# wmc.net
KiCad netlist of a schematic drawn in EAGLE
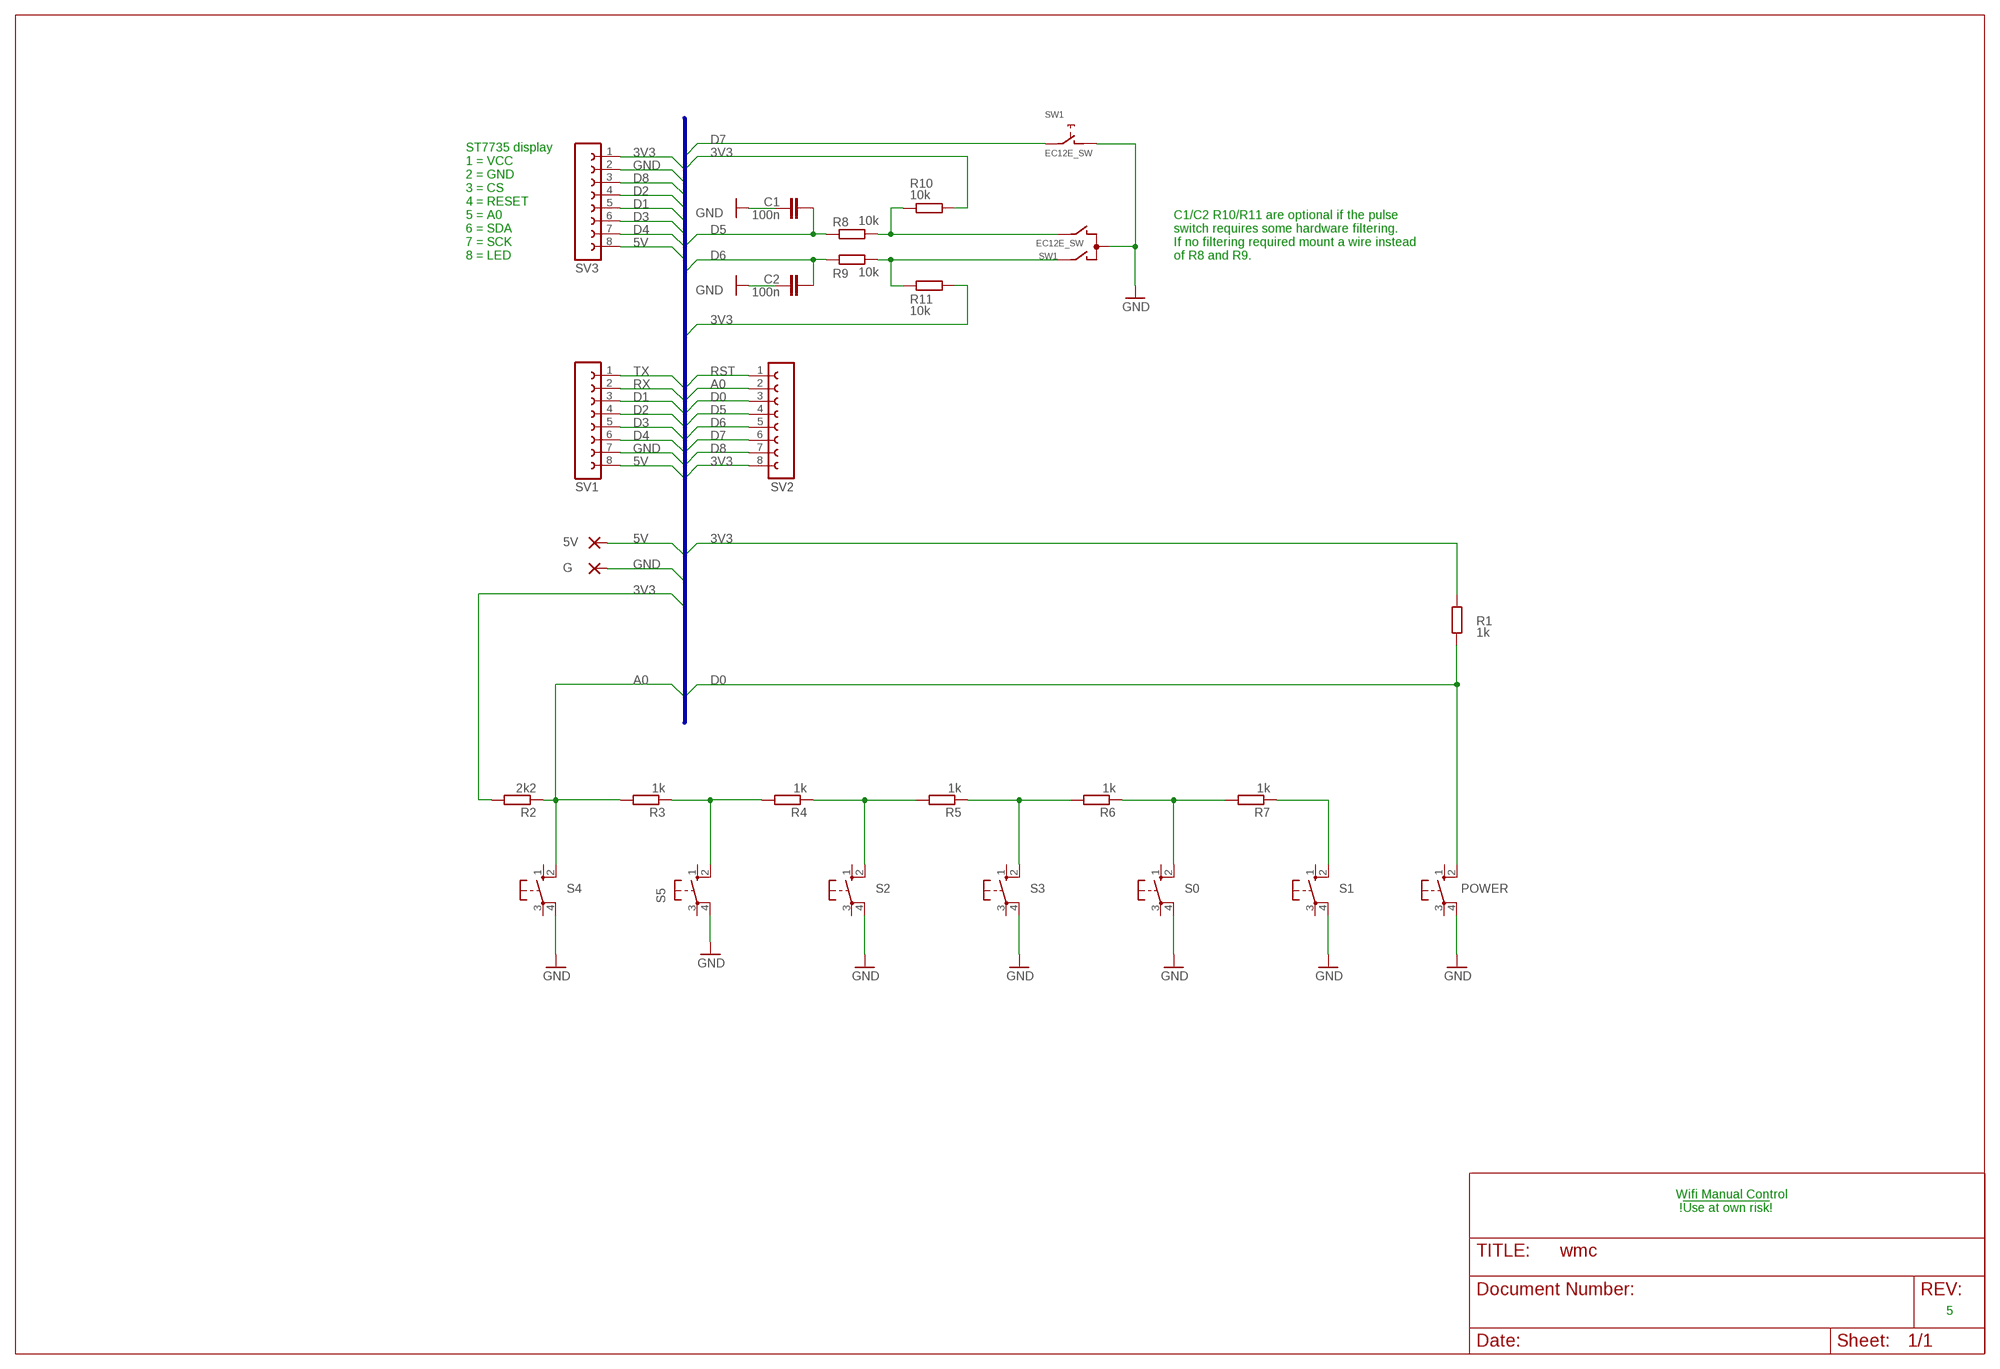
[diagram p0: schematic, sheet 1]

(export (version "E")
  (design (tool "Eeschema 10.0.6"))
  (components
    (comp (ref "5V")
      (value "1,6/0,8")
      (footprint "eagle-import:1,6_0,8")
      (libsource (lib "eagle-import") (part "1,6/0,8"))
    )
    (comp (ref "C1")
      (value "100n")
      (footprint "eagle-import:C025-024X044")
      (libsource (lib "eagle-import") (part "C-EU025-024X044"))
    )
    (comp (ref "C2")
      (value "100n")
      (footprint "eagle-import:C025-024X044")
      (libsource (lib "eagle-import") (part "C-EU025-024X044"))
    )
    (comp (ref "G")
      (value "1,6/0,8")
      (footprint "eagle-import:1,6_0,8")
      (libsource (lib "eagle-import") (part "1,6/0,8"))
    )
    (comp (ref "POWER")
      (value "10-XX")
      (footprint "eagle-import:B3F-10XX")
      (fields (field (name "MPN") "B3F-1000"))
      (libsource (lib "eagle-import") (part "10-XX"))
    )
    (comp (ref "R1")
      (value "1k")
      (footprint "eagle-import:0309_10")
      (libsource (lib "eagle-import") (part "R-EU_0309/10"))
    )
    (comp (ref "R2")
      (value "2k2")
      (footprint "eagle-import:0309_10")
      (libsource (lib "eagle-import") (part "R-EU_0309/10"))
    )
    (comp (ref "R3")
      (value "1k")
      (footprint "eagle-import:0309_10")
      (libsource (lib "eagle-import") (part "R-EU_0309/10"))
    )
    (comp (ref "R4")
      (value "1k")
      (footprint "eagle-import:0309_10")
      (libsource (lib "eagle-import") (part "R-EU_0309/10"))
    )
    (comp (ref "R5")
      (value "1k")
      (footprint "eagle-import:0309_10")
      (libsource (lib "eagle-import") (part "R-EU_0309/10"))
    )
    (comp (ref "R6")
      (value "1k")
      (footprint "eagle-import:0309_10")
      (libsource (lib "eagle-import") (part "R-EU_0309/10"))
    )
    (comp (ref "R7")
      (value "1k")
      (footprint "eagle-import:0309_10")
      (libsource (lib "eagle-import") (part "R-EU_0309/10"))
    )
    (comp (ref "R8")
      (value "10k")
      (footprint "eagle-import:0207_10")
      (libsource (lib "eagle-import") (part "rcl_334_R-EU_0207/10"))
    )
    (comp (ref "R9")
      (value "10k")
      (footprint "eagle-import:0207_10")
      (libsource (lib "eagle-import") (part "rcl_334_R-EU_0207/10"))
    )
    (comp (ref "R10")
      (value "10k")
      (footprint "eagle-import:0207_10")
      (libsource (lib "eagle-import") (part "rcl_334_R-EU_0207/10"))
    )
    (comp (ref "R11")
      (value "10k")
      (footprint "eagle-import:0207_10")
      (libsource (lib "eagle-import") (part "rcl_334_R-EU_0207/10"))
    )
    (comp (ref "S0")
      (value "10-XX")
      (footprint "eagle-import:B3F-10XX")
      (fields (field (name "MPN") "B3F-1000"))
      (libsource (lib "eagle-import") (part "10-XX"))
    )
    (comp (ref "S1")
      (value "10-XX")
      (footprint "eagle-import:B3F-10XX")
      (fields (field (name "MPN") "B3F-1000"))
      (libsource (lib "eagle-import") (part "10-XX"))
    )
    (comp (ref "S2")
      (value "10-XX")
      (footprint "eagle-import:B3F-10XX")
      (fields (field (name "MPN") "B3F-1000"))
      (libsource (lib "eagle-import") (part "10-XX"))
    )
    (comp (ref "S3")
      (value "10-XX")
      (footprint "eagle-import:B3F-10XX")
      (fields (field (name "MPN") "B3F-1000"))
      (libsource (lib "eagle-import") (part "10-XX"))
    )
    (comp (ref "S4")
      (value "10-XX")
      (footprint "eagle-import:B3F-10XX")
      (fields (field (name "MPN") "B3F-1000"))
      (libsource (lib "eagle-import") (part "10-XX"))
    )
    (comp (ref "S5")
      (value "10-XX")
      (footprint "eagle-import:B3F-10XX")
      (fields (field (name "MPN") "B3F-1000"))
      (libsource (lib "eagle-import") (part "10-XX"))
    )
    (comp (ref "SV1")
      (value "FE08-1")
      (footprint "eagle-import:FE08")
      (libsource (lib "eagle-import") (part "FE08-1"))
    )
    (comp (ref "SV2")
      (value "FE08-1")
      (footprint "eagle-import:FE08")
      (libsource (lib "eagle-import") (part "FE08-1"))
    )
    (comp (ref "SV3")
      (value "FE08-1")
      (footprint "eagle-import:FE08")
      (libsource (lib "eagle-import") (part "FE08-1"))
    )
    (comp (ref "SW1")
      (value "EC12E_SW")
      (footprint "eagle-import:ALPS_EC12E_SW")
      (fields (field (name "MPN") "EC12E2424407"))
      (libsource (lib "eagle-import") (part "EC12E_SW"))
    )
  )
  (nets
    (net (code "1") (name "/3V3") (class "Default")
      (node (ref "R1") (pin "2") (pinfunction "2_2") (pintype "passive"))
      (node (ref "R10") (pin "2") (pinfunction "2_2") (pintype "passive"))
      (node (ref "R11") (pin "2") (pinfunction "2_2") (pintype "passive"))
      (node (ref "R2") (pin "2") (pinfunction "2_2") (pintype "passive"))
      (node (ref "SV2") (pin "8") (pinfunction "8_8") (pintype "passive"))
      (node (ref "SV3") (pin "1") (pinfunction "1_1") (pintype "passive"))
    )
    (net (code "2") (name "/5V") (class "Default")
      (node (ref "5V") (pin "1") (pinfunction "P_1") (pintype "passive"))
      (node (ref "SV1") (pin "8") (pinfunction "8_8") (pintype "passive"))
      (node (ref "SV3") (pin "8") (pinfunction "8_8") (pintype "passive"))
    )
    (net (code "3") (name "/A0") (class "Default")
      (node (ref "R2") (pin "1") (pinfunction "1_1") (pintype "passive"))
      (node (ref "R3") (pin "2") (pinfunction "2_2") (pintype "passive"))
      (node (ref "S4") (pin "2") (pinfunction "S1_2") (pintype "passive"))
      (node (ref "SV2") (pin "2") (pinfunction "2_2") (pintype "passive"))
    )
    (net (code "4") (name "/D0") (class "Default")
      (node (ref "POWER") (pin "2") (pinfunction "S1_2") (pintype "passive"))
      (node (ref "R1") (pin "1") (pinfunction "1_1") (pintype "passive"))
      (node (ref "SV2") (pin "3") (pinfunction "3_3") (pintype "passive"))
    )
    (net (code "5") (name "/D1") (class "Default")
      (node (ref "SV1") (pin "3") (pinfunction "3_3") (pintype "passive"))
      (node (ref "SV3") (pin "5") (pinfunction "5_5") (pintype "passive"))
    )
    (net (code "6") (name "/D2") (class "Default")
      (node (ref "SV1") (pin "4") (pinfunction "4_4") (pintype "passive"))
      (node (ref "SV3") (pin "4") (pinfunction "4_4") (pintype "passive"))
    )
    (net (code "7") (name "/D3") (class "Default")
      (node (ref "SV1") (pin "5") (pinfunction "5_5") (pintype "passive"))
      (node (ref "SV3") (pin "6") (pinfunction "6_6") (pintype "passive"))
    )
    (net (code "8") (name "/D4") (class "Default")
      (node (ref "SV1") (pin "6") (pinfunction "6_6") (pintype "passive"))
      (node (ref "SV3") (pin "7") (pinfunction "7_7") (pintype "passive"))
    )
    (net (code "9") (name "/D5") (class "Default")
      (node (ref "C1") (pin "1") (pinfunction "1_1") (pintype "passive"))
      (node (ref "R8") (pin "1") (pinfunction "1_1") (pintype "passive"))
      (node (ref "SV2") (pin "4") (pinfunction "4_4") (pintype "passive"))
    )
    (net (code "10") (name "/D6") (class "Default")
      (node (ref "C2") (pin "1") (pinfunction "1_1") (pintype "passive"))
      (node (ref "R9") (pin "1") (pinfunction "1_1") (pintype "passive"))
      (node (ref "SV2") (pin "5") (pinfunction "5_5") (pintype "passive"))
    )
    (net (code "11") (name "/D7") (class "Default")
      (node (ref "SV2") (pin "6") (pinfunction "6_6") (pintype "passive"))
      (node (ref "SW1") (pin "E") (pinfunction "2_E") (pintype "passive"))
    )
    (net (code "12") (name "/D8") (class "Default")
      (node (ref "SV2") (pin "7") (pinfunction "7_7") (pintype "passive"))
      (node (ref "SV3") (pin "3") (pinfunction "3_3") (pintype "passive"))
    )
    (net (code "13") (name "/RST") (class "Default")
      (node (ref "SV2") (pin "1") (pinfunction "1_1") (pintype "passive"))
    )
    (net (code "14") (name "/RX") (class "Default")
      (node (ref "SV1") (pin "2") (pinfunction "2_2") (pintype "passive"))
    )
    (net (code "15") (name "/TX") (class "Default")
      (node (ref "SV1") (pin "1") (pinfunction "1_1") (pintype "passive"))
    )
    (net (code "16") (name "GND") (class "Default")
      (node (ref "C1") (pin "2") (pinfunction "2_2") (pintype "passive"))
      (node (ref "C2") (pin "2") (pinfunction "2_2") (pintype "passive"))
      (node (ref "G") (pin "1") (pinfunction "P_1") (pintype "passive"))
      (node (ref "POWER") (pin "4") (pinfunction "P1_4") (pintype "passive"))
      (node (ref "S0") (pin "4") (pinfunction "P1_4") (pintype "passive"))
      (node (ref "S1") (pin "4") (pinfunction "P1_4") (pintype "passive"))
      (node (ref "S2") (pin "4") (pinfunction "P1_4") (pintype "passive"))
      (node (ref "S3") (pin "4") (pinfunction "P1_4") (pintype "passive"))
      (node (ref "S4") (pin "4") (pinfunction "P1_4") (pintype "passive"))
      (node (ref "S5") (pin "4") (pinfunction "P1_4") (pintype "passive"))
      (node (ref "SV1") (pin "7") (pinfunction "7_7") (pintype "passive"))
      (node (ref "SV3") (pin "2") (pinfunction "2_2") (pintype "passive"))
      (node (ref "SW1") (pin "C") (pinfunction "C_C") (pintype "passive"))
      (node (ref "SW1") (pin "D") (pinfunction "1_D") (pintype "passive"))
    )
    (net (code "17") (name "Net-(R10-Pad1)") (class "Default")
      (node (ref "R10") (pin "1") (pinfunction "1_1") (pintype "passive"))
      (node (ref "R8") (pin "2") (pinfunction "2_2") (pintype "passive"))
      (node (ref "SW1") (pin "B") (pinfunction "B_B") (pintype "passive"))
    )
    (net (code "18") (name "Net-(R11-Pad1)") (class "Default")
      (node (ref "R11") (pin "1") (pinfunction "1_1") (pintype "passive"))
      (node (ref "R9") (pin "2") (pinfunction "2_2") (pintype "passive"))
      (node (ref "SW1") (pin "A") (pinfunction "A_A") (pintype "passive"))
    )
    (net (code "19") (name "Net-(S0-S1)") (class "Default")
      (node (ref "R6") (pin "1") (pinfunction "1_1") (pintype "passive"))
      (node (ref "R7") (pin "2") (pinfunction "2_2") (pintype "passive"))
      (node (ref "S0") (pin "2") (pinfunction "S1_2") (pintype "passive"))
    )
    (net (code "20") (name "Net-(S1-S1)") (class "Default")
      (node (ref "R7") (pin "1") (pinfunction "1_1") (pintype "passive"))
      (node (ref "S1") (pin "2") (pinfunction "S1_2") (pintype "passive"))
    )
    (net (code "21") (name "Net-(S2-S1)") (class "Default")
      (node (ref "R4") (pin "1") (pinfunction "1_1") (pintype "passive"))
      (node (ref "R5") (pin "2") (pinfunction "2_2") (pintype "passive"))
      (node (ref "S2") (pin "2") (pinfunction "S1_2") (pintype "passive"))
    )
    (net (code "22") (name "Net-(S3-S1)") (class "Default")
      (node (ref "R5") (pin "1") (pinfunction "1_1") (pintype "passive"))
      (node (ref "R6") (pin "2") (pinfunction "2_2") (pintype "passive"))
      (node (ref "S3") (pin "2") (pinfunction "S1_2") (pintype "passive"))
    )
    (net (code "23") (name "Net-(S5-S1)") (class "Default")
      (node (ref "R3") (pin "1") (pinfunction "1_1") (pintype "passive"))
      (node (ref "R4") (pin "2") (pinfunction "2_2") (pintype "passive"))
      (node (ref "S5") (pin "2") (pinfunction "S1_2") (pintype "passive"))
    )
    (net (code "24") (name "unconnected-(POWER-P-Pad3)") (class "Default")
      (node (ref "POWER") (pin "3") (pinfunction "P_3") (pintype "passive"))
    )
    (net (code "25") (name "unconnected-(POWER-S-Pad1)") (class "Default")
      (node (ref "POWER") (pin "1") (pinfunction "S_1") (pintype "passive"))
    )
    (net (code "26") (name "unconnected-(S0-P-Pad3)") (class "Default")
      (node (ref "S0") (pin "3") (pinfunction "P_3") (pintype "passive"))
    )
    (net (code "27") (name "unconnected-(S0-S-Pad1)") (class "Default")
      (node (ref "S0") (pin "1") (pinfunction "S_1") (pintype "passive"))
    )
    (net (code "28") (name "unconnected-(S1-P-Pad3)") (class "Default")
      (node (ref "S1") (pin "3") (pinfunction "P_3") (pintype "passive"))
    )
    (net (code "29") (name "unconnected-(S1-S-Pad1)") (class "Default")
      (node (ref "S1") (pin "1") (pinfunction "S_1") (pintype "passive"))
    )
    (net (code "30") (name "unconnected-(S2-P-Pad3)") (class "Default")
      (node (ref "S2") (pin "3") (pinfunction "P_3") (pintype "passive"))
    )
    (net (code "31") (name "unconnected-(S2-S-Pad1)") (class "Default")
      (node (ref "S2") (pin "1") (pinfunction "S_1") (pintype "passive"))
    )
    (net (code "32") (name "unconnected-(S3-P-Pad3)") (class "Default")
      (node (ref "S3") (pin "3") (pinfunction "P_3") (pintype "passive"))
    )
    (net (code "33") (name "unconnected-(S3-S-Pad1)") (class "Default")
      (node (ref "S3") (pin "1") (pinfunction "S_1") (pintype "passive"))
    )
    (net (code "34") (name "unconnected-(S4-P-Pad3)") (class "Default")
      (node (ref "S4") (pin "3") (pinfunction "P_3") (pintype "passive"))
    )
    (net (code "35") (name "unconnected-(S4-S-Pad1)") (class "Default")
      (node (ref "S4") (pin "1") (pinfunction "S_1") (pintype "passive"))
    )
    (net (code "36") (name "unconnected-(S5-P-Pad3)") (class "Default")
      (node (ref "S5") (pin "3") (pinfunction "P_3") (pintype "passive"))
    )
    (net (code "37") (name "unconnected-(S5-S-Pad1)") (class "Default")
      (node (ref "S5") (pin "1") (pinfunction "S_1") (pintype "passive"))
    )
  )
)
